# DAC2.net
KiCad netlist of a schematic drawn in EAGLE
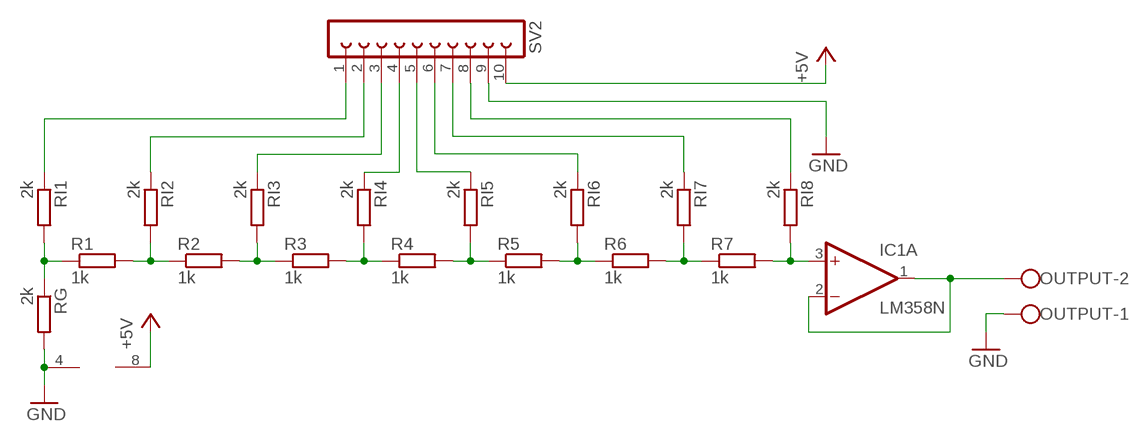
[diagram p0: schematic, sheet 1]

(export (version "E")
  (design (tool "Eeschema 10.0.6"))
  (components
    (comp (ref "IC1")
      (value "LM358N")
      (footprint "eagle-import:DIL08")
      (libsource (lib "eagle-import") (part "LM358N"))
    )
    (comp (ref "OUTPUT")
      (value "W237-102")
      (footprint "eagle-import:W237-102")
      (fields (field (name "MPN") "237-102"))
      (libsource (lib "eagle-import") (part "W237-102"))
    )
    (comp (ref "R1")
      (value "1k")
      (footprint "eagle-import:0207_12")
      (libsource (lib "eagle-import") (part "R-EU_0207/12"))
    )
    (comp (ref "R2")
      (value "1k")
      (footprint "eagle-import:0207_12")
      (libsource (lib "eagle-import") (part "R-EU_0207/12"))
    )
    (comp (ref "R3")
      (value "1k")
      (footprint "eagle-import:0207_12")
      (libsource (lib "eagle-import") (part "R-EU_0207/12"))
    )
    (comp (ref "R4")
      (value "1k")
      (footprint "eagle-import:0207_12")
      (libsource (lib "eagle-import") (part "R-EU_0207/12"))
    )
    (comp (ref "R5")
      (value "1k")
      (footprint "eagle-import:0207_12")
      (libsource (lib "eagle-import") (part "R-EU_0207/12"))
    )
    (comp (ref "R6")
      (value "1k")
      (footprint "eagle-import:0207_12")
      (libsource (lib "eagle-import") (part "R-EU_0207/12"))
    )
    (comp (ref "R7")
      (value "1k")
      (footprint "eagle-import:0207_12")
      (libsource (lib "eagle-import") (part "R-EU_0207/12"))
    )
    (comp (ref "RG")
      (value "2k")
      (footprint "eagle-import:0207_12")
      (libsource (lib "eagle-import") (part "R-EU_0207/12"))
    )
    (comp (ref "RI1")
      (value "2k")
      (footprint "eagle-import:0207_12")
      (libsource (lib "eagle-import") (part "R-EU_0207/12"))
    )
    (comp (ref "RI2")
      (value "2k")
      (footprint "eagle-import:0207_12")
      (libsource (lib "eagle-import") (part "R-EU_0207/12"))
    )
    (comp (ref "RI3")
      (value "2k")
      (footprint "eagle-import:0207_12")
      (libsource (lib "eagle-import") (part "R-EU_0207/12"))
    )
    (comp (ref "RI4")
      (value "2k")
      (footprint "eagle-import:0207_12")
      (libsource (lib "eagle-import") (part "R-EU_0207/12"))
    )
    (comp (ref "RI5")
      (value "2k")
      (footprint "eagle-import:0207_12")
      (libsource (lib "eagle-import") (part "R-EU_0207/12"))
    )
    (comp (ref "RI6")
      (value "2k")
      (footprint "eagle-import:0207_12")
      (libsource (lib "eagle-import") (part "R-EU_0207/12"))
    )
    (comp (ref "RI7")
      (value "2k")
      (footprint "eagle-import:0207_12")
      (libsource (lib "eagle-import") (part "R-EU_0207/12"))
    )
    (comp (ref "RI8")
      (value "2k")
      (footprint "eagle-import:0207_12")
      (libsource (lib "eagle-import") (part "R-EU_0207/12"))
    )
    (comp (ref "SV2")
      (value "FE10-1")
      (footprint "eagle-import:FE10")
      (libsource (lib "eagle-import") (part "FE10-1"))
    )
  )
  (nets
    (net (code "1") (name "+5V") (class "Default")
      (node (ref "IC1") (pin "8") (pinfunction "V+_8") (pintype "power_in"))
      (node (ref "SV2") (pin "10") (pinfunction "10_10") (pintype "passive"))
    )
    (net (code "2") (name "GND") (class "Default")
      (node (ref "IC1") (pin "4") (pinfunction "V-_4") (pintype "power_in"))
      (node (ref "OUTPUT") (pin "1") (pinfunction "KL_1") (pintype "passive"))
      (node (ref "RG") (pin "2") (pinfunction "2_2") (pintype "passive"))
      (node (ref "SV2") (pin "9") (pinfunction "9_9") (pintype "passive"))
    )
    (net (code "3") (name "Net-(IC1A-+IN)") (class "Default")
      (node (ref "IC1") (pin "3") (pinfunction "+IN_3") (pintype "input"))
      (node (ref "R7") (pin "2") (pinfunction "2_2") (pintype "passive"))
      (node (ref "RI8") (pin "2") (pinfunction "2_2") (pintype "passive"))
    )
    (net (code "4") (name "Net-(IC1A--IN)") (class "Default")
      (node (ref "IC1") (pin "1") (pinfunction "OUT_1") (pintype "output"))
      (node (ref "IC1") (pin "2") (pinfunction "-IN_2") (pintype "input"))
      (node (ref "OUTPUT") (pin "2") (pinfunction "KL_2") (pintype "passive"))
    )
    (net (code "5") (name "Net-(R1-Pad1)") (class "Default")
      (node (ref "R1") (pin "1") (pinfunction "1_1") (pintype "passive"))
      (node (ref "RG") (pin "1") (pinfunction "1_1") (pintype "passive"))
      (node (ref "RI1") (pin "2") (pinfunction "2_2") (pintype "passive"))
    )
    (net (code "6") (name "Net-(R1-Pad2)") (class "Default")
      (node (ref "R1") (pin "2") (pinfunction "2_2") (pintype "passive"))
      (node (ref "R2") (pin "1") (pinfunction "1_1") (pintype "passive"))
      (node (ref "RI2") (pin "2") (pinfunction "2_2") (pintype "passive"))
    )
    (net (code "7") (name "Net-(R2-Pad2)") (class "Default")
      (node (ref "R2") (pin "2") (pinfunction "2_2") (pintype "passive"))
      (node (ref "R3") (pin "1") (pinfunction "1_1") (pintype "passive"))
      (node (ref "RI3") (pin "2") (pinfunction "2_2") (pintype "passive"))
    )
    (net (code "8") (name "Net-(R3-Pad2)") (class "Default")
      (node (ref "R3") (pin "2") (pinfunction "2_2") (pintype "passive"))
      (node (ref "R4") (pin "1") (pinfunction "1_1") (pintype "passive"))
      (node (ref "RI4") (pin "2") (pinfunction "2_2") (pintype "passive"))
    )
    (net (code "9") (name "Net-(R4-Pad2)") (class "Default")
      (node (ref "R4") (pin "2") (pinfunction "2_2") (pintype "passive"))
      (node (ref "R5") (pin "1") (pinfunction "1_1") (pintype "passive"))
      (node (ref "RI5") (pin "2") (pinfunction "2_2") (pintype "passive"))
    )
    (net (code "10") (name "Net-(R5-Pad2)") (class "Default")
      (node (ref "R5") (pin "2") (pinfunction "2_2") (pintype "passive"))
      (node (ref "R6") (pin "1") (pinfunction "1_1") (pintype "passive"))
      (node (ref "RI6") (pin "2") (pinfunction "2_2") (pintype "passive"))
    )
    (net (code "11") (name "Net-(R6-Pad2)") (class "Default")
      (node (ref "R6") (pin "2") (pinfunction "2_2") (pintype "passive"))
      (node (ref "R7") (pin "1") (pinfunction "1_1") (pintype "passive"))
      (node (ref "RI7") (pin "2") (pinfunction "2_2") (pintype "passive"))
    )
    (net (code "12") (name "Net-(RI1-Pad1)") (class "Default")
      (node (ref "RI1") (pin "1") (pinfunction "1_1") (pintype "passive"))
      (node (ref "SV2") (pin "1") (pinfunction "1_1") (pintype "passive"))
    )
    (net (code "13") (name "Net-(RI2-Pad1)") (class "Default")
      (node (ref "RI2") (pin "1") (pinfunction "1_1") (pintype "passive"))
      (node (ref "SV2") (pin "2") (pinfunction "2_2") (pintype "passive"))
    )
    (net (code "14") (name "Net-(RI3-Pad1)") (class "Default")
      (node (ref "RI3") (pin "1") (pinfunction "1_1") (pintype "passive"))
      (node (ref "SV2") (pin "3") (pinfunction "3_3") (pintype "passive"))
    )
    (net (code "15") (name "Net-(RI4-Pad1)") (class "Default")
      (node (ref "RI4") (pin "1") (pinfunction "1_1") (pintype "passive"))
      (node (ref "SV2") (pin "4") (pinfunction "4_4") (pintype "passive"))
    )
    (net (code "16") (name "Net-(RI5-Pad1)") (class "Default")
      (node (ref "RI5") (pin "1") (pinfunction "1_1") (pintype "passive"))
      (node (ref "SV2") (pin "5") (pinfunction "5_5") (pintype "passive"))
    )
    (net (code "17") (name "Net-(RI6-Pad1)") (class "Default")
      (node (ref "RI6") (pin "1") (pinfunction "1_1") (pintype "passive"))
      (node (ref "SV2") (pin "6") (pinfunction "6_6") (pintype "passive"))
    )
    (net (code "18") (name "Net-(RI7-Pad1)") (class "Default")
      (node (ref "RI7") (pin "1") (pinfunction "1_1") (pintype "passive"))
      (node (ref "SV2") (pin "7") (pinfunction "7_7") (pintype "passive"))
    )
    (net (code "19") (name "Net-(RI8-Pad1)") (class "Default")
      (node (ref "RI8") (pin "1") (pinfunction "1_1") (pintype "passive"))
      (node (ref "SV2") (pin "8") (pinfunction "8_8") (pintype "passive"))
    )
  )
)
